# 1_Power_Supply.net
KiCad netlist of a schematic drawn in Altium Designer
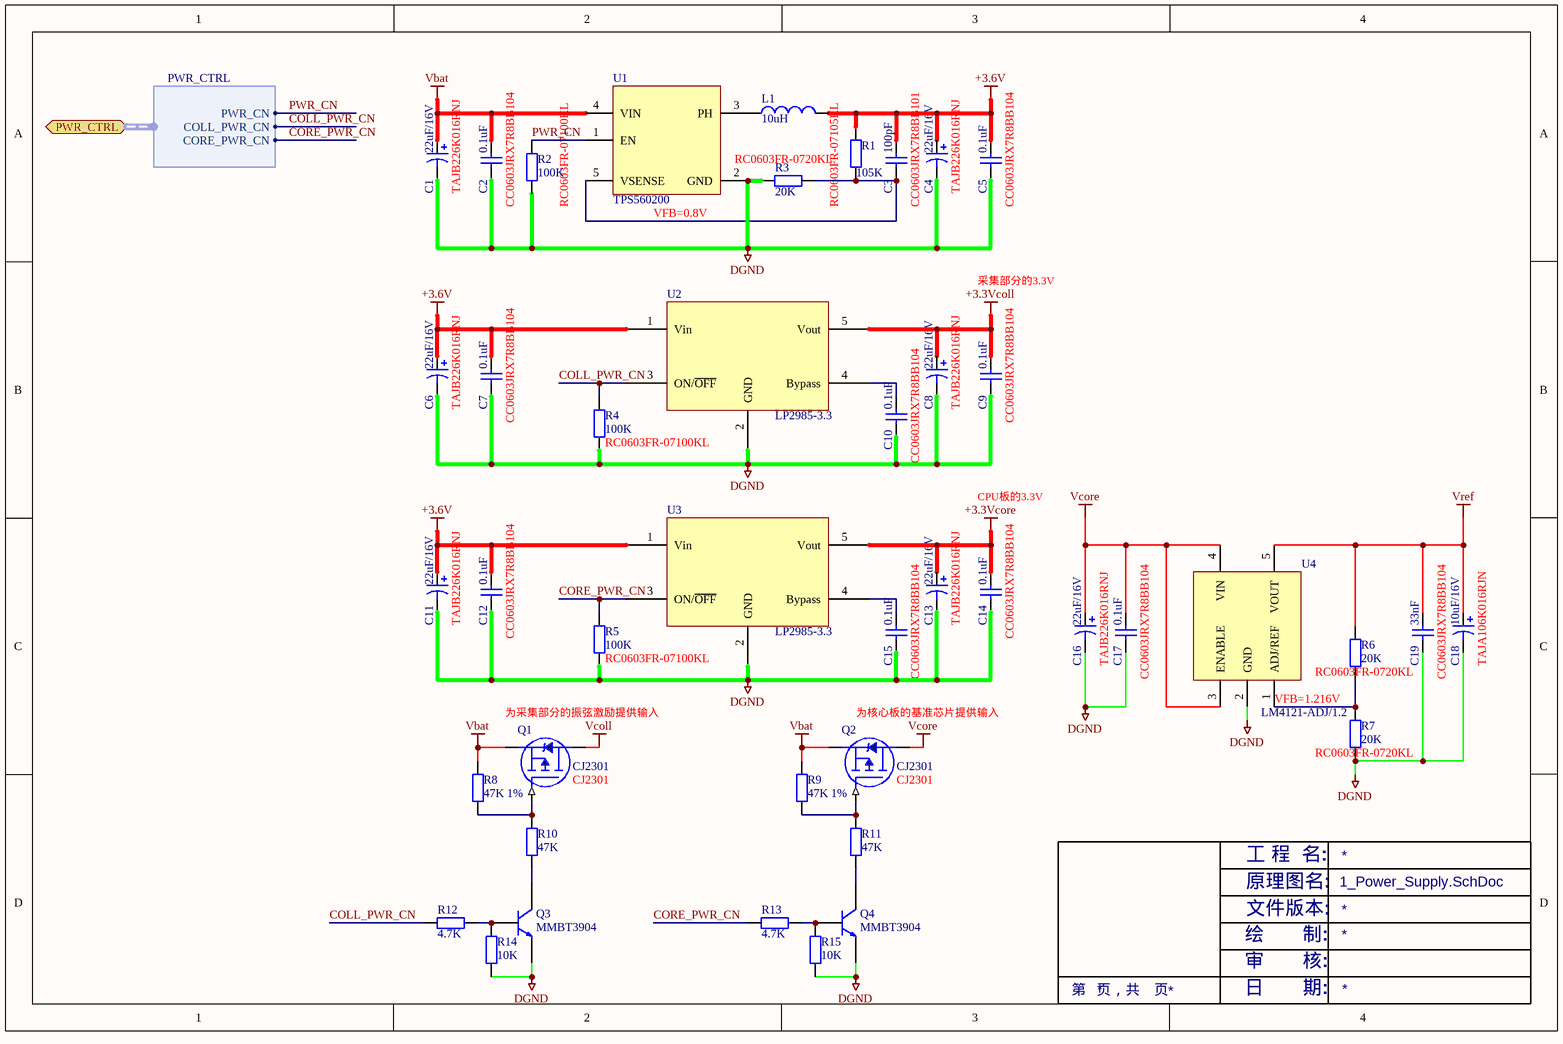
[diagram p0: 1_Power_Supply.SchDoc]

(export (version "E")
  (design (tool "Eeschema 10.0.6"))
  (components
    (comp (ref "C1")
      (value "22uF/16V")
      (footprint "CB3528")
      (description "Polarized Capacitor (Radial)")
      (fields (field (name "PART NO.") "TAJB226K016RNJ"))
      (libsource (lib "Miscellaneous Devices") (part "Cap Pol1"))
    )
    (comp (ref "C2")
      (value "0.1uF")
      (footprint "CC0603")
      (description "Capacitor")
      (fields (field (name "TYPE NO.") "CC0603JRX7R8BB104"))
      (libsource (lib "Miscellaneous Devices") (part "Cap"))
    )
    (comp (ref "C3")
      (value "100pF")
      (footprint "CC0603")
      (description "Capacitor")
      (fields (field (name "TYPE NO.") "CC0603JRX7R8BB101"))
      (libsource (lib "Miscellaneous Devices") (part "Cap"))
    )
    (comp (ref "C4")
      (value "22uF/16V")
      (footprint "CB3528")
      (description "Polarized Capacitor (Radial)")
      (fields (field (name "PART NO.") "TAJB226K016RNJ"))
      (libsource (lib "Miscellaneous Devices") (part "Cap Pol1"))
    )
    (comp (ref "C5")
      (value "0.1uF")
      (footprint "CC0603")
      (description "Capacitor")
      (fields (field (name "TYPE NO.") "CC0603JRX7R8BB104"))
      (libsource (lib "Miscellaneous Devices") (part "Cap"))
    )
    (comp (ref "C6")
      (value "22uF/16V")
      (footprint "CB3528")
      (description "Polarized Capacitor (Radial)")
      (fields (field (name "PART NO.") "TAJB226K016RNJ"))
      (libsource (lib "Miscellaneous Devices") (part "Cap Pol1"))
    )
    (comp (ref "C7")
      (value "0.1uF")
      (footprint "CC0603")
      (description "Capacitor")
      (fields (field (name "TYPE NO.") "CC0603JRX7R8BB104"))
      (libsource (lib "Miscellaneous Devices") (part "Cap"))
    )
    (comp (ref "C8")
      (value "22uF/16V")
      (footprint "CB3528")
      (description "Polarized Capacitor (Radial)")
      (fields (field (name "PART NO.") "TAJB226K016RNJ"))
      (libsource (lib "Miscellaneous Devices") (part "Cap Pol1"))
    )
    (comp (ref "C9")
      (value "0.1uF")
      (footprint "CC0603")
      (description "Capacitor")
      (fields (field (name "TYPE NO.") "CC0603JRX7R8BB104"))
      (libsource (lib "Miscellaneous Devices") (part "Cap"))
    )
    (comp (ref "C10")
      (value "0.1uF")
      (footprint "CC0603")
      (description "Capacitor")
      (fields (field (name "TYPE NO.") "CC0603JRX7R8BB104"))
      (libsource (lib "Miscellaneous Devices") (part "Cap"))
    )
    (comp (ref "C11")
      (value "22uF/16V")
      (footprint "CB3528")
      (description "Polarized Capacitor (Radial)")
      (fields (field (name "PART NO.") "TAJB226K016RNJ"))
      (libsource (lib "Miscellaneous Devices") (part "Cap Pol1"))
    )
    (comp (ref "C12")
      (value "0.1uF")
      (footprint "CC0603")
      (description "Capacitor")
      (fields (field (name "TYPE NO.") "CC0603JRX7R8BB104"))
      (libsource (lib "Miscellaneous Devices") (part "Cap"))
    )
    (comp (ref "C13")
      (value "22uF/16V")
      (footprint "CB3528")
      (description "Polarized Capacitor (Radial)")
      (fields (field (name "PART NO.") "TAJB226K016RNJ"))
      (libsource (lib "Miscellaneous Devices") (part "Cap Pol1"))
    )
    (comp (ref "C14")
      (value "0.1uF")
      (footprint "CC0603")
      (description "Capacitor")
      (fields (field (name "TYPE NO.") "CC0603JRX7R8BB104"))
      (libsource (lib "Miscellaneous Devices") (part "Cap"))
    )
    (comp (ref "C15")
      (value "0.1uF")
      (footprint "CC0603")
      (description "Capacitor")
      (fields (field (name "TYPE NO.") "CC0603JRX7R8BB104"))
      (libsource (lib "Miscellaneous Devices") (part "Cap"))
    )
    (comp (ref "C16")
      (value "22uF/16V")
      (footprint "CB3528")
      (description "Polarized Capacitor (Radial)")
      (fields (field (name "PART NO.") "TAJB226K016RNJ"))
      (libsource (lib "Miscellaneous Devices") (part "Cap Pol1"))
    )
    (comp (ref "C17")
      (value "0.1uF")
      (footprint "CC0603")
      (description "Capacitor")
      (fields (field (name "TYPE NO.") "CC0603JRX7R8BB104"))
      (libsource (lib "Miscellaneous Devices") (part "Cap"))
    )
    (comp (ref "C18")
      (value "10uF/16V")
      (footprint "CA3216")
      (description "Polarized Capacitor (Radial)")
      (fields (field (name "TYPE NO.") "TAJA106K016RJN"))
      (libsource (lib "Miscellaneous Devices") (part "Cap Pol1"))
    )
    (comp (ref "C19")
      (value "33nF")
      (footprint "CC0603")
      (description "Capacitor")
      (fields (field (name "TYPE NO.") "CC0603JRX7R8BB104"))
      (libsource (lib "Miscellaneous Devices") (part "Cap"))
    )
    (comp (ref "L1")
      (value "10uH")
      (footprint "SLF6025")
      (description "Inductor")
      (fields (field (name "PUBLISHER") "Altium Limited"))
      (libsource (lib "Miscellaneous Devices") (part "Inductor"))
    )
    (comp (ref "Q1")
      (value "CJ2301")
      (footprint "SOT-23W")
      (fields (field (name "TYPE NO.") "CJ2301"))
      (libsource (lib "woylib2015") (part "P-MOSFET1"))
    )
    (comp (ref "Q2")
      (value "CJ2301")
      (footprint "SOT-23W")
      (fields (field (name "TYPE NO.") "CJ2301"))
      (libsource (lib "woylib2015") (part "P-MOSFET1"))
    )
    (comp (ref "Q3") (value "MMBT3904") (footprint "SOT-23W") (libsource (lib "woylib2015") (part "NPN")))
    (comp (ref "Q4") (value "MMBT3904") (footprint "SOT-23W") (libsource (lib "woylib2015") (part "NPN")))
    (comp (ref "R1")
      (value "105K")
      (footprint "CC0603")
      (description "Resistor")
      (fields (field (name "TYPE NO.") "RC0603FR-07105KL"))
      (libsource (lib "Miscellaneous Devices") (part "Res2"))
    )
    (comp (ref "R2")
      (value "100K")
      (footprint "CC0603")
      (description "Resistor")
      (fields (field (name "TYPE NO.") "RC0603FR-07100KL"))
      (libsource (lib "Miscellaneous Devices") (part "Res2"))
    )
    (comp (ref "R3")
      (value "20K")
      (footprint "CC0603")
      (description "Resistor")
      (fields (field (name "TYPE NO.") "RC0603FR-0720KL"))
      (libsource (lib "") (part "Res2_2"))
    )
    (comp (ref "R4")
      (value "100K")
      (footprint "CC0603")
      (description "Resistor")
      (fields (field (name "TYPE NO.") "RC0603FR-07100KL"))
      (libsource (lib "Miscellaneous Devices") (part "Res2"))
    )
    (comp (ref "R5")
      (value "100K")
      (footprint "CC0603")
      (description "Resistor")
      (fields (field (name "TYPE NO.") "RC0603FR-07100KL"))
      (libsource (lib "Miscellaneous Devices") (part "Res2"))
    )
    (comp (ref "R6")
      (value "20K")
      (footprint "CC0603")
      (description "Resistor")
      (fields (field (name "TYPE NO.") "RC0603FR-0720KL"))
      (libsource (lib "Miscellaneous Devices") (part "Res2"))
    )
    (comp (ref "R7")
      (value "20K")
      (footprint "CC0603")
      (description "Resistor")
      (fields (field (name "TYPE NO.") "RC0603FR-0720KL"))
      (libsource (lib "Miscellaneous Devices") (part "Res2"))
    )
    (comp (ref "R8")
      (value "47K 1%")
      (footprint "CC0603")
      (description "Resistor")
      (fields (field (name "PUBLISHER") "Altium Limited"))
      (libsource (lib "Miscellaneous Devices") (part "Res2"))
    )
    (comp (ref "R9")
      (value "47K 1%")
      (footprint "CC0603")
      (description "Resistor")
      (fields (field (name "PUBLISHER") "Altium Limited"))
      (libsource (lib "Miscellaneous Devices") (part "Res2"))
    )
    (comp (ref "R10")
      (value "47K")
      (footprint "CC0603")
      (description "Resistor")
      (fields (field (name "PUBLISHER") "Altium Limited"))
      (libsource (lib "Miscellaneous Devices") (part "Res2"))
    )
    (comp (ref "R11")
      (value "47K")
      (footprint "CC0603")
      (description "Resistor")
      (fields (field (name "PUBLISHER") "Altium Limited"))
      (libsource (lib "Miscellaneous Devices") (part "Res2"))
    )
    (comp (ref "R12")
      (value "4.7K")
      (footprint "CC0603")
      (description "Resistor")
      (fields (field (name "PUBLISHER") "Altium Limited"))
      (libsource (lib "") (part "Res2_1"))
    )
    (comp (ref "R13")
      (value "4.7K")
      (footprint "CC0603")
      (description "Resistor")
      (fields (field (name "PUBLISHER") "Altium Limited"))
      (libsource (lib "") (part "Res2_1"))
    )
    (comp (ref "R14")
      (value "10K")
      (footprint "CC0603")
      (description "Resistor")
      (fields (field (name "PUBLISHER") "Altium Limited"))
      (libsource (lib "Miscellaneous Devices") (part "Res2"))
    )
    (comp (ref "R15")
      (value "10K")
      (footprint "CC0603")
      (description "Resistor")
      (fields (field (name "PUBLISHER") "Altium Limited"))
      (libsource (lib "Miscellaneous Devices") (part "Res2"))
    )
    (comp (ref "U1") (value "TPS560200") (footprint "SOT-23-5") (libsource (lib "IC") (part "TPS560200")))
    (comp (ref "U2") (value "LP2985-3.3") (footprint "SOT-23-5") (libsource (lib "IC") (part "LP2985")))
    (comp (ref "U3") (value "LP2985-3.3") (footprint "SOT-23-5") (libsource (lib "IC") (part "LP2985")))
    (comp (ref "U4")
      (value "LM4121-ADJ/1.2")
      (footprint "IC-SMT:SOT-23-5")
      (libsource (lib "IC") (part "LM4121-ADJ/1.2"))
    )
  )
  (nets
    (net (code "2") (name "+3.3Vcoll") (class "Default")
      (node (ref "C8") (pin "1") (pinfunction "1_1") (pintype "passive"))
      (node (ref "C9") (pin "2") (pinfunction "2_2") (pintype "passive"))
      (node (ref "U2") (pin "5") (pinfunction "Vout_5") (pintype "passive"))
    )
    (net (code "3") (name "+3.3Vcore") (class "Default")
      (node (ref "C13") (pin "1") (pinfunction "1_1") (pintype "passive"))
      (node (ref "C14") (pin "2") (pinfunction "2_2") (pintype "passive"))
      (node (ref "U3") (pin "5") (pinfunction "Vout_5") (pintype "passive"))
    )
    (net (code "4") (name "+3.6V") (class "Default")
      (node (ref "C11") (pin "1") (pinfunction "1_1") (pintype "passive"))
      (node (ref "C12") (pin "2") (pinfunction "2_2") (pintype "passive"))
      (node (ref "C3") (pin "2") (pinfunction "2_2") (pintype "passive"))
      (node (ref "C4") (pin "1") (pinfunction "1_1") (pintype "passive"))
      (node (ref "C5") (pin "2") (pinfunction "2_2") (pintype "passive"))
      (node (ref "C6") (pin "1") (pinfunction "1_1") (pintype "passive"))
      (node (ref "C7") (pin "2") (pinfunction "2_2") (pintype "passive"))
      (node (ref "L1") (pin "2") (pinfunction "2_2") (pintype "passive"))
      (node (ref "R1") (pin "1") (pinfunction "1_1") (pintype "passive"))
      (node (ref "U2") (pin "1") (pinfunction "Vin_1") (pintype "passive"))
      (node (ref "U3") (pin "1") (pinfunction "Vin_1") (pintype "passive"))
    )
    (net (code "5") (name "/COLL_PWR_CN") (class "Default")
      (node (ref "R12") (pin "1") (pinfunction "1_1") (pintype "passive"))
      (node (ref "R4") (pin "1") (pinfunction "1_1") (pintype "passive"))
      (node (ref "U2") (pin "3") (pinfunction "ON/~{OFF}_3") (pintype "passive"))
    )
    (net (code "6") (name "/CORE_PWR_CN") (class "Default")
      (node (ref "R13") (pin "1") (pinfunction "1_1") (pintype "passive"))
      (node (ref "R5") (pin "1") (pinfunction "1_1") (pintype "passive"))
      (node (ref "U3") (pin "3") (pinfunction "ON/~{OFF}_3") (pintype "passive"))
    )
    (net (code "7") (name "/PWR_CN") (class "Default")
      (node (ref "R2") (pin "1") (pinfunction "1_1") (pintype "passive"))
      (node (ref "U1") (pin "1") (pinfunction "EN_1") (pintype "passive"))
    )
    (net (code "9") (name "DGND") (class "Default")
      (node (ref "C1") (pin "2") (pinfunction "2_2") (pintype "passive"))
      (node (ref "C10") (pin "1") (pinfunction "1_1") (pintype "passive"))
      (node (ref "C11") (pin "2") (pinfunction "2_2") (pintype "passive"))
      (node (ref "C12") (pin "1") (pinfunction "1_1") (pintype "passive"))
      (node (ref "C13") (pin "2") (pinfunction "2_2") (pintype "passive"))
      (node (ref "C14") (pin "1") (pinfunction "1_1") (pintype "passive"))
      (node (ref "C15") (pin "1") (pinfunction "1_1") (pintype "passive"))
      (node (ref "C16") (pin "2") (pinfunction "2_2") (pintype "passive"))
      (node (ref "C17") (pin "1") (pinfunction "1_1") (pintype "passive"))
      (node (ref "C18") (pin "2") (pinfunction "2_2") (pintype "passive"))
      (node (ref "C19") (pin "1") (pinfunction "1_1") (pintype "passive"))
      (node (ref "C2") (pin "1") (pinfunction "1_1") (pintype "passive"))
      (node (ref "C4") (pin "2") (pinfunction "2_2") (pintype "passive"))
      (node (ref "C5") (pin "1") (pinfunction "1_1") (pintype "passive"))
      (node (ref "C6") (pin "2") (pinfunction "2_2") (pintype "passive"))
      (node (ref "C7") (pin "1") (pinfunction "1_1") (pintype "passive"))
      (node (ref "C8") (pin "2") (pinfunction "2_2") (pintype "passive"))
      (node (ref "C9") (pin "1") (pinfunction "1_1") (pintype "passive"))
      (node (ref "Q3") (pin "2") (pinfunction "2_2") (pintype "passive"))
      (node (ref "Q4") (pin "2") (pinfunction "2_2") (pintype "passive"))
      (node (ref "R14") (pin "2") (pinfunction "2_2") (pintype "passive"))
      (node (ref "R15") (pin "2") (pinfunction "2_2") (pintype "passive"))
      (node (ref "R2") (pin "2") (pinfunction "2_2") (pintype "passive"))
      (node (ref "R3") (pin "2") (pinfunction "2_2") (pintype "passive"))
      (node (ref "R4") (pin "2") (pinfunction "2_2") (pintype "passive"))
      (node (ref "R5") (pin "2") (pinfunction "2_2") (pintype "passive"))
      (node (ref "R7") (pin "2") (pinfunction "2_2") (pintype "passive"))
      (node (ref "U1") (pin "2") (pinfunction "GND_2") (pintype "passive"))
      (node (ref "U2") (pin "2") (pinfunction "GND_2") (pintype "passive"))
      (node (ref "U3") (pin "2") (pinfunction "GND_2") (pintype "passive"))
      (node (ref "U4") (pin "2") (pinfunction "GND_2") (pintype "passive"))
    )
    (net (code "10") (name "Net-(Q1-GATE)") (class "Default")
      (node (ref "Q1") (pin "1") (pinfunction "GATE_1") (pintype "input"))
      (node (ref "R10") (pin "1") (pinfunction "1_1") (pintype "passive"))
      (node (ref "R8") (pin "2") (pinfunction "2_2") (pintype "passive"))
    )
    (net (code "11") (name "Net-(Q2-GATE)") (class "Default")
      (node (ref "Q2") (pin "1") (pinfunction "GATE_1") (pintype "input"))
      (node (ref "R11") (pin "1") (pinfunction "1_1") (pintype "passive"))
      (node (ref "R9") (pin "2") (pinfunction "2_2") (pintype "passive"))
    )
    (net (code "12") (name "Net-(Q3-Pad1)") (class "Default")
      (node (ref "Q3") (pin "1") (pinfunction "1_1") (pintype "passive"))
      (node (ref "R12") (pin "2") (pinfunction "2_2") (pintype "passive"))
      (node (ref "R14") (pin "1") (pinfunction "1_1") (pintype "passive"))
    )
    (net (code "13") (name "Net-(Q3-Pad3)") (class "Default")
      (node (ref "Q3") (pin "3") (pinfunction "3_3") (pintype "passive"))
      (node (ref "R10") (pin "2") (pinfunction "2_2") (pintype "passive"))
    )
    (net (code "14") (name "Net-(Q4-Pad1)") (class "Default")
      (node (ref "Q4") (pin "1") (pinfunction "1_1") (pintype "passive"))
      (node (ref "R13") (pin "2") (pinfunction "2_2") (pintype "passive"))
      (node (ref "R15") (pin "1") (pinfunction "1_1") (pintype "passive"))
    )
    (net (code "15") (name "Net-(Q4-Pad3)") (class "Default")
      (node (ref "Q4") (pin "3") (pinfunction "3_3") (pintype "passive"))
      (node (ref "R11") (pin "2") (pinfunction "2_2") (pintype "passive"))
    )
    (net (code "16") (name "Net-(U1-PH)") (class "Default")
      (node (ref "L1") (pin "1") (pinfunction "1_1") (pintype "passive"))
      (node (ref "U1") (pin "3") (pinfunction "PH_3") (pintype "passive"))
    )
    (net (code "17") (name "Net-(U1-VSENSE)") (class "Default")
      (node (ref "C3") (pin "1") (pinfunction "1_1") (pintype "passive"))
      (node (ref "R1") (pin "2") (pinfunction "2_2") (pintype "passive"))
      (node (ref "R3") (pin "1") (pinfunction "1_1") (pintype "passive"))
      (node (ref "U1") (pin "5") (pinfunction "VSENSE_5") (pintype "passive"))
    )
    (net (code "18") (name "Net-(U2-Bypass)") (class "Default")
      (node (ref "C10") (pin "2") (pinfunction "2_2") (pintype "passive"))
      (node (ref "U2") (pin "4") (pinfunction "Bypass_4") (pintype "passive"))
    )
    (net (code "19") (name "Net-(U3-Bypass)") (class "Default")
      (node (ref "C15") (pin "2") (pinfunction "2_2") (pintype "passive"))
      (node (ref "U3") (pin "4") (pinfunction "Bypass_4") (pintype "passive"))
    )
    (net (code "20") (name "Net-(U4-ADJ{slash}REF)") (class "Default")
      (node (ref "R6") (pin "2") (pinfunction "2_2") (pintype "passive"))
      (node (ref "R7") (pin "1") (pinfunction "1_1") (pintype "passive"))
      (node (ref "U4") (pin "1") (pinfunction "ADJ/REF_1") (pintype "passive"))
    )
    (net (code "21") (name "Vbat") (class "Default")
      (node (ref "C1") (pin "1") (pinfunction "1_1") (pintype "passive"))
      (node (ref "C2") (pin "2") (pinfunction "2_2") (pintype "passive"))
      (node (ref "Q1") (pin "2") (pinfunction "SOURCE_2") (pintype "passive"))
      (node (ref "Q2") (pin "2") (pinfunction "SOURCE_2") (pintype "passive"))
      (node (ref "R8") (pin "1") (pinfunction "1_1") (pintype "passive"))
      (node (ref "R9") (pin "1") (pinfunction "1_1") (pintype "passive"))
      (node (ref "U1") (pin "4") (pinfunction "VIN_4") (pintype "passive"))
    )
    (net (code "22") (name "Vcoll") (class "Default")
      (node (ref "Q1") (pin "3") (pinfunction "DRAIN_3") (pintype "passive"))
    )
    (net (code "23") (name "Vcore") (class "Default")
      (node (ref "C16") (pin "1") (pinfunction "1_1") (pintype "passive"))
      (node (ref "C17") (pin "2") (pinfunction "2_2") (pintype "passive"))
      (node (ref "Q2") (pin "3") (pinfunction "DRAIN_3") (pintype "passive"))
      (node (ref "U4") (pin "3") (pinfunction "ENABLE_3") (pintype "passive"))
      (node (ref "U4") (pin "4") (pinfunction "VIN_4") (pintype "passive"))
    )
    (net (code "24") (name "Vref") (class "Default")
      (node (ref "C18") (pin "1") (pinfunction "1_1") (pintype "passive"))
      (node (ref "C19") (pin "2") (pinfunction "2_2") (pintype "passive"))
      (node (ref "R6") (pin "1") (pinfunction "1_1") (pintype "passive"))
      (node (ref "U4") (pin "5") (pinfunction "VOUT_5") (pintype "passive"))
    )
  )
)
